# modbusbox.net
KiCad netlist of a schematic drawn in EAGLE
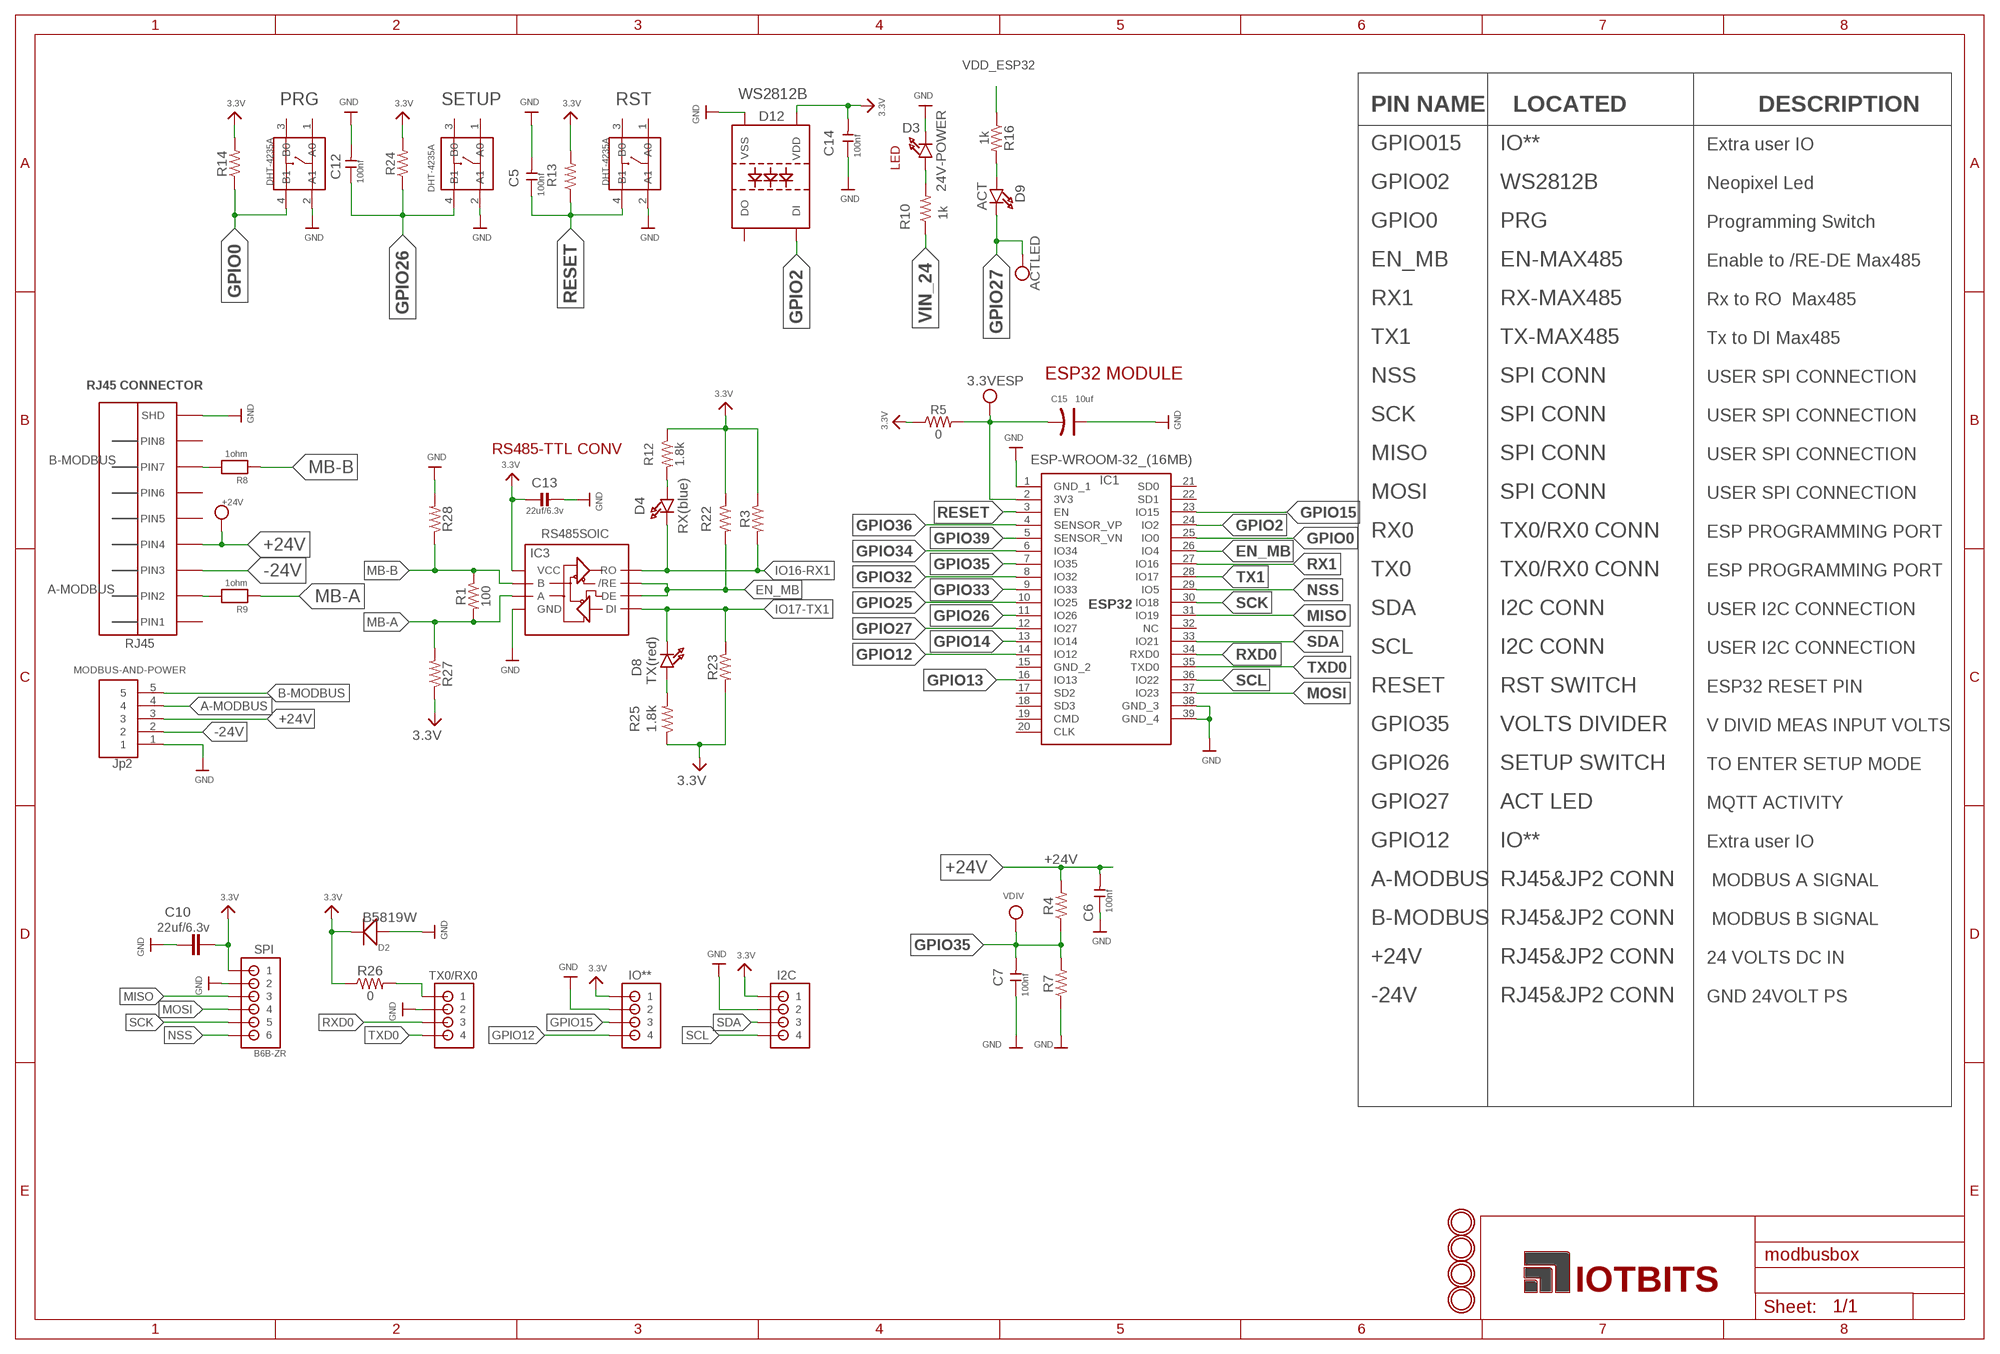
[diagram p0: schematic, sheet 1]

(export (version "E")
  (design (tool "Eeschema 10.0.6"))
  (components
    (comp (ref "+24V")
      (value "TESTPOINTROUND2MM")
      (footprint "eagle-import:TESTPOINT_ROUND_2MM")
      (libsource (lib "eagle-import") (part "TESTPOINTROUND2MM"))
    )
    (comp (ref "3.3VESP")
      (value "TESTPOINTROUND2MM")
      (footprint "eagle-import:TESTPOINT_ROUND_2MM")
      (libsource (lib "eagle-import") (part "TESTPOINTROUND2MM"))
    )
    (comp (ref "ACTLED")
      (value "TESTPOINTROUND2MM")
      (footprint "eagle-import:TESTPOINT_ROUND_2MM")
      (libsource (lib "eagle-import") (part "TESTPOINTROUND2MM"))
    )
    (comp (ref "C5")
      (value "100nf")
      (footprint "eagle-import:C0603")
      (fields (field (name "MPN") "CC0603KRX7R9BB104") (field (name "SPICEPREFIX") "C"))
      (libsource (lib "eagle-import") (part "CERAMIC-100NF-50V-10%-X7R(0603)"))
    )
    (comp (ref "C6")
      (value "100nf")
      (footprint "eagle-import:C0603")
      (fields (field (name "MPN") "CC0603KRX7R9BB104"))
      (libsource (lib "eagle-import") (part "CERAMIC-100NF-50V-10%-X7R(0603)"))
    )
    (comp (ref "C7")
      (value "100nf")
      (footprint "eagle-import:C0603")
      (fields (field (name "MPN") "CC0603KRX7R9BB104"))
      (libsource (lib "eagle-import") (part "CERAMIC-100NF-50V-10%-X7R(0603)"))
    )
    (comp (ref "C10")
      (value "22uf/6.3v")
      (footprint "eagle-import:0805-CAP-LARGEPADS")
      (libsource (lib "eagle-import") (part "CAP0805-CAP-LARGEPADS"))
    )
    (comp (ref "C12")
      (value "100nf")
      (footprint "eagle-import:C0603")
      (fields (field (name "MPN") "CC0603KRX7R9BB104") (field (name "SPICEPREFIX") "C"))
      (libsource (lib "eagle-import") (part "CERAMIC-100NF-50V-10%-X7R(0603)"))
    )
    (comp (ref "C13")
      (value "22uf/6.3v")
      (footprint "eagle-import:_0805")
      (libsource (lib "eagle-import") (part "CAP_CERAMIC_0805"))
    )
    (comp (ref "C14")
      (value "100nf")
      (footprint "eagle-import:C0603")
      (fields (field (name "MPN") "CC0603KRX7R9BB104"))
      (libsource (lib "eagle-import") (part "CERAMIC-100NF-50V-10%-X7R(0603)"))
    )
    (comp (ref "C15")
      (value "10uf")
      (footprint "eagle-import:AVX-A")
      (fields (field (name "MPN") "TAJA106K010RNJ"))
      (libsource (lib "eagle-import") (part "TANTALUM-SMD-10UF-10V-10%(AVX-A)"))
    )
    (comp (ref "D2")
      (value "B5819W")
      (footprint "eagle-import:SOD-123")
      (libsource (lib "eagle-import") (part "SMD-DIODE-SCHOTTKY-20V-1A(SOD-123)"))
    )
    (comp (ref "D3")
      (value "24V-POWER")
      (footprint "eagle-import:CHIPLED_0603")
      (libsource (lib "eagle-import") (part "LED0603"))
    )
    (comp (ref "D4")
      (value "RX(blue)")
      (footprint "eagle-import:CHIPLED_0603")
      (libsource (lib "eagle-import") (part "LED0603"))
    )
    (comp (ref "D8")
      (value "TX(red)")
      (footprint "eagle-import:CHIPLED_0603")
      (libsource (lib "eagle-import") (part "LED0603"))
    )
    (comp (ref "D9")
      (value "ACT")
      (footprint "eagle-import:CHIPLED_0603")
      (libsource (lib "eagle-import") (part "LED0603"))
    )
    (comp (ref "D12")
      (value "WS2812B")
      (footprint "eagle-import:WS2812B")
      (libsource (lib "eagle-import") (part "WS2812B"))
    )
    (comp (ref "I2C")
      (value "B4B-ZR")
      (footprint "eagle-import:B4B-ZR")
      (libsource (lib "eagle-import") (part "B4B-ZR"))
    )
    (comp (ref "IC1")
      (value "ESP-WROOM-32_(16MB)")
      (footprint "eagle-import:ESP32WROOM32D")
      (fields
        (field (name "MANUFACTURER_PART_NUMBER") "ESP-WROOM-32 (16MB)")
        (field (name "MOUSER_PART_NUMBER") "356-ESPWROOM3216MB")
      )
      (libsource (lib "eagle-import") (part "ESP-WROOM-32_(16MB)"))
    )
    (comp (ref "IC3")
      (value "RS485SOIC")
      (footprint "eagle-import:SO08")
      (libsource (lib "eagle-import") (part "RS485SOIC"))
    )
    (comp (ref "IO**")
      (value "B4B-ZR")
      (footprint "eagle-import:B4B-ZR")
      (libsource (lib "eagle-import") (part "B4B-ZR"))
    )
    (comp (ref "MODBUS-AND-POWER")
      (value "5PIN")
      (footprint "eagle-import:B5B-PH-K-S")
      (libsource (lib "eagle-import") (part "5PIN"))
    )
    (comp (ref "PRG")
      (value "DHT-4235A")
      (footprint "eagle-import:SW4-SMD-4.2X3.2X2.5MM")
      (fields (field (name "SPICEPREFIX") "E"))
      (libsource (lib "eagle-import") (part "SMD-BUTTON-TOP-DHT-4235A(4P-4.2X3.2MM)"))
    )
    (comp (ref "R1")
      (value "100")
      (footprint "eagle-import:0603")
      (libsource (lib "eagle-import") (part "100OHM-0603-1/4W-5%"))
    )
    (comp (ref "R3")
      (value "10KOHM-0603-1/10W-1%")
      (footprint "eagle-import:0603")
      (libsource (lib "eagle-import") (part "10KOHM-0603-1/10W-1%"))
    )
    (comp (ref "R4")
      (value "100k")
      (footprint "eagle-import:0603")
      (libsource (lib "eagle-import") (part "10KOHM-0603-1/10W-1%"))
    )
    (comp (ref "R5")
      (value "0")
      (footprint "eagle-import:0603")
      (libsource (lib "eagle-import") (part "0OHM-0603-1/10W-5%"))
    )
    (comp (ref "R7")
      (value "15k")
      (footprint "eagle-import:0603")
      (libsource (lib "eagle-import") (part "10KOHM-0603-1/10W-1%"))
    )
    (comp (ref "R8")
      (value "1ohm")
      (footprint "eagle-import:0603")
      (libsource (lib "eagle-import") (part "RESISTOR0603"))
    )
    (comp (ref "R9")
      (value "1ohm")
      (footprint "eagle-import:0603")
      (libsource (lib "eagle-import") (part "RESISTOR0603"))
    )
    (comp (ref "R10")
      (value "1k")
      (footprint "eagle-import:0603")
      (libsource (lib "eagle-import") (part "1KOHM-0603-1/10W-1%"))
    )
    (comp (ref "R12")
      (value "1.8k")
      (footprint "eagle-import:0603")
      (libsource (lib "eagle-import") (part "1.8KOHM-0603-1/10W-1%"))
    )
    (comp (ref "R13")
      (value "10KOHM-0603-1/10W-1%")
      (footprint "eagle-import:0603")
      (fields (field (name "SPICEPREFIX") "R"))
      (libsource (lib "eagle-import") (part "10KOHM-0603-1/10W-1%"))
    )
    (comp (ref "R14")
      (value "10KOHM-0603-1/10W-1%")
      (footprint "eagle-import:0603")
      (fields (field (name "SPICEPREFIX") "R"))
      (libsource (lib "eagle-import") (part "10KOHM-0603-1/10W-1%"))
    )
    (comp (ref "R16")
      (value "1k")
      (footprint "eagle-import:0603")
      (libsource (lib "eagle-import") (part "1KOHM-0603-1/10W-1%"))
    )
    (comp (ref "R22")
      (value "10KOHM-0603-1/10W-1%")
      (footprint "eagle-import:0603")
      (libsource (lib "eagle-import") (part "10KOHM-0603-1/10W-1%"))
    )
    (comp (ref "R23")
      (value "10KOHM-0603-1/10W-1%")
      (footprint "eagle-import:0603")
      (libsource (lib "eagle-import") (part "10KOHM-0603-1/10W-1%"))
    )
    (comp (ref "R24")
      (value "10KOHM-0603-1/10W-1%")
      (footprint "eagle-import:0603")
      (fields (field (name "SPICEPREFIX") "R"))
      (libsource (lib "eagle-import") (part "10KOHM-0603-1/10W-1%"))
    )
    (comp (ref "R25")
      (value "1.8k")
      (footprint "eagle-import:0603")
      (libsource (lib "eagle-import") (part "1.8KOHM-0603-1/10W-1%"))
    )
    (comp (ref "R26")
      (value "0")
      (footprint "eagle-import:0603")
      (libsource (lib "eagle-import") (part "0OHM-0603-1/10W-5%"))
    )
    (comp (ref "R27")
      (value "2.2k")
      (footprint "eagle-import:0603")
      (libsource (lib "eagle-import") (part "10KOHM-0603-1/10W-1%"))
    )
    (comp (ref "R28")
      (value "2.2k")
      (footprint "eagle-import:0603")
      (libsource (lib "eagle-import") (part "10KOHM-0603-1/10W-1%"))
    )
    (comp (ref "RJ45")
      (value "RJ45 CONNECTOR")
      (footprint "eagle-import:RJ45")
      (libsource (lib "eagle-import") (part "RJ45"))
    )
    (comp (ref "RST")
      (value "DHT-4235A")
      (footprint "eagle-import:SW4-SMD-4.2X3.2X2.5MM")
      (fields (field (name "SPICEPREFIX") "E"))
      (libsource (lib "eagle-import") (part "SMD-BUTTON-TOP-DHT-4235A(4P-4.2X3.2MM)"))
    )
    (comp (ref "SETUP")
      (value "DHT-4235A")
      (footprint "eagle-import:SW4-SMD-4.2X3.2X2.5MM")
      (fields (field (name "SPICEPREFIX") "S"))
      (libsource (lib "eagle-import") (part "SMD-BUTTON-TOP-DHT-4235A(4P-4.2X3.2MM)"))
    )
    (comp (ref "SPI")
      (value "B6B-ZR")
      (footprint "eagle-import:B6B-ZR")
      (libsource (lib "eagle-import") (part "B6B-ZR"))
    )
    (comp (ref "TX0/RX0")
      (value "B4B-ZR")
      (footprint "eagle-import:B4B-ZR")
      (libsource (lib "eagle-import") (part "B4B-ZR"))
    )
    (comp (ref "U$30")
      (value "MOUNTINGHOLE3.0THIN")
      (footprint "eagle-import:MOUNTINGHOLE_3.0_PLATEDTHIN")
      (libsource (lib "eagle-import") (part "MOUNTINGHOLE3.0THIN"))
    )
    (comp (ref "U$31")
      (value "MOUNTINGHOLE3.0THIN")
      (footprint "eagle-import:MOUNTINGHOLE_3.0_PLATEDTHIN")
      (libsource (lib "eagle-import") (part "MOUNTINGHOLE3.0THIN"))
    )
    (comp (ref "U$33")
      (value "MOUNTINGHOLE3.0THIN")
      (footprint "eagle-import:MOUNTINGHOLE_3.0_PLATEDTHIN")
      (libsource (lib "eagle-import") (part "MOUNTINGHOLE3.0THIN"))
    )
    (comp (ref "U$35")
      (value "MOUNTINGHOLE3.0THIN")
      (footprint "eagle-import:MOUNTINGHOLE_3.0_PLATEDTHIN")
      (libsource (lib "eagle-import") (part "MOUNTINGHOLE3.0THIN"))
    )
    (comp (ref "VDIV")
      (value "TESTPOINTROUND2MM")
      (footprint "eagle-import:TESTPOINT_ROUND_2MM")
      (libsource (lib "eagle-import") (part "TESTPOINTROUND2MM"))
    )
  )
  (nets
    (net (code "1") (name "+24V") (class "Default")
      (node (ref "+24V") (pin "P$1") (pinfunction "P$1_P$1") (pintype "bidirectional"))
      (node (ref "C6") (pin "2") (pinfunction "2_2") (pintype "passive"))
      (node (ref "MODBUS-AND-POWER") (pin "3") (pinfunction "3_3") (pintype "bidirectional"))
      (node (ref "R4") (pin "2") (pinfunction "2_2") (pintype "passive"))
      (node (ref "RJ45") (pin "P$10") (pinfunction "PIN4_P$10") (pintype "bidirectional"))
    )
    (net (code "2") (name "-24V") (class "Default")
      (node (ref "MODBUS-AND-POWER") (pin "2") (pinfunction "2_2") (pintype "bidirectional"))
      (node (ref "RJ45") (pin "P$9") (pinfunction "PIN3_P$9") (pintype "bidirectional"))
    )
    (net (code "3") (name "/VDD_ESP32") (class "Default")
      (node (ref "3.3VESP") (pin "P$1") (pinfunction "P$1_P$1") (pintype "bidirectional"))
      (node (ref "C15") (pin "-") (pinfunction "-_-") (pintype "passive"))
      (node (ref "IC1") (pin "2") (pinfunction "3V3_2") (pintype "bidirectional"))
      (node (ref "R16") (pin "1") (pinfunction "1_1") (pintype "passive"))
      (node (ref "R5") (pin "2") (pinfunction "2_2") (pintype "passive"))
    )
    (net (code "4") (name "3.3V") (class "Default")
      (node (ref "C10") (pin "1") (pinfunction "1_1") (pintype "passive"))
      (node (ref "C13") (pin "1") (pinfunction "1_1") (pintype "passive"))
      (node (ref "C14") (pin "2") (pinfunction "2_2") (pintype "passive"))
      (node (ref "D12") (pin "1") (pinfunction "VDD_1") (pintype "bidirectional"))
      (node (ref "D2") (pin "-") (pinfunction "-_-") (pintype "passive"))
      (node (ref "I2C") (pin "1") (pinfunction "1_1") (pintype "bidirectional"))
      (node (ref "IC3") (pin "8") (pinfunction "VCC_8") (pintype "bidirectional"))
      (node (ref "IO**") (pin "1") (pinfunction "1_1") (pintype "bidirectional"))
      (node (ref "R12") (pin "1") (pinfunction "1_1") (pintype "passive"))
      (node (ref "R13") (pin "2") (pinfunction "2_2") (pintype "passive"))
      (node (ref "R14") (pin "2") (pinfunction "2_2") (pintype "passive"))
      (node (ref "R22") (pin "1") (pinfunction "1_1") (pintype "passive"))
      (node (ref "R23") (pin "2") (pinfunction "2_2") (pintype "passive"))
      (node (ref "R24") (pin "2") (pinfunction "2_2") (pintype "passive"))
      (node (ref "R25") (pin "1") (pinfunction "1_1") (pintype "passive"))
      (node (ref "R26") (pin "1") (pinfunction "1_1") (pintype "passive"))
      (node (ref "R27") (pin "1") (pinfunction "1_1") (pintype "passive"))
      (node (ref "R3") (pin "1") (pinfunction "1_1") (pintype "passive"))
      (node (ref "R5") (pin "1") (pinfunction "1_1") (pintype "passive"))
      (node (ref "SPI") (pin "1") (pinfunction "1_1") (pintype "bidirectional"))
    )
    (net (code "5") (name "A-MODBUS") (class "Default")
      (node (ref "MODBUS-AND-POWER") (pin "4") (pinfunction "4_4") (pintype "bidirectional"))
      (node (ref "R9") (pin "2") (pinfunction "2_2") (pintype "passive"))
      (node (ref "RJ45") (pin "P$3") (pinfunction "PIN2_P$3") (pintype "bidirectional"))
    )
    (net (code "6") (name "B-MODBUS") (class "Default")
      (node (ref "MODBUS-AND-POWER") (pin "5") (pinfunction "5_5") (pintype "bidirectional"))
      (node (ref "R8") (pin "2") (pinfunction "2_2") (pintype "passive"))
      (node (ref "RJ45") (pin "P$6") (pinfunction "PIN7_P$6") (pintype "bidirectional"))
    )
    (net (code "7") (name "EN_MB") (class "Default")
      (node (ref "IC1") (pin "26") (pinfunction "IO4_26") (pintype "bidirectional"))
      (node (ref "IC3") (pin "2") (pinfunction "/RE_2") (pintype "bidirectional"))
      (node (ref "IC3") (pin "3") (pinfunction "DE_3") (pintype "bidirectional"))
      (node (ref "R22") (pin "2") (pinfunction "2_2") (pintype "passive"))
    )
    (net (code "8") (name "GND") (class "Default")
      (node (ref "C10") (pin "2") (pinfunction "2_2") (pintype "passive"))
      (node (ref "C12") (pin "2") (pinfunction "2_2") (pintype "passive"))
      (node (ref "C13") (pin "2") (pinfunction "2_2") (pintype "passive"))
      (node (ref "C14") (pin "1") (pinfunction "1_1") (pintype "passive"))
      (node (ref "C15") (pin "+") (pinfunction "+_+") (pintype "passive"))
      (node (ref "C5") (pin "2") (pinfunction "2_2") (pintype "passive"))
      (node (ref "C6") (pin "1") (pinfunction "1_1") (pintype "passive"))
      (node (ref "C7") (pin "1") (pinfunction "1_1") (pintype "passive"))
      (node (ref "D12") (pin "3") (pinfunction "VSS_3") (pintype "bidirectional"))
      (node (ref "D2") (pin "+") (pinfunction "+_+") (pintype "passive"))
      (node (ref "D3") (pin "C") (pinfunction "C_C") (pintype "passive"))
      (node (ref "I2C") (pin "2") (pinfunction "2_2") (pintype "bidirectional"))
      (node (ref "IC1") (pin "1") (pinfunction "GND_1_1") (pintype "bidirectional"))
      (node (ref "IC1") (pin "38") (pinfunction "GND_3_38") (pintype "bidirectional"))
      (node (ref "IC1") (pin "39") (pinfunction "GND_4_39") (pintype "bidirectional"))
      (node (ref "IC3") (pin "5") (pinfunction "GND_5") (pintype "bidirectional"))
      (node (ref "IO**") (pin "2") (pinfunction "2_2") (pintype "bidirectional"))
      (node (ref "MODBUS-AND-POWER") (pin "1") (pinfunction "1_1") (pintype "bidirectional"))
      (node (ref "PRG") (pin "2") (pinfunction "A1_2") (pintype "bidirectional"))
      (node (ref "R28") (pin "2") (pinfunction "2_2") (pintype "passive"))
      (node (ref "R7") (pin "1") (pinfunction "1_1") (pintype "passive"))
      (node (ref "RJ45") (pin "P$1") (pinfunction "SHD_P$1") (pintype "bidirectional"))
      (node (ref "RJ45") (pin "P$2") (pinfunction "SHD_P$2") (pintype "bidirectional"))
      (node (ref "RST") (pin "2") (pinfunction "A1_2") (pintype "bidirectional"))
      (node (ref "SETUP") (pin "2") (pinfunction "A1_2") (pintype "bidirectional"))
      (node (ref "SPI") (pin "2") (pinfunction "2_2") (pintype "bidirectional"))
      (node (ref "TX0/RX0") (pin "2") (pinfunction "2_2") (pintype "bidirectional"))
    )
    (net (code "9") (name "GPIO0") (class "Default")
      (node (ref "IC1") (pin "25") (pinfunction "IO0_25") (pintype "bidirectional"))
      (node (ref "PRG") (pin "4") (pinfunction "B1_4") (pintype "bidirectional"))
      (node (ref "R14") (pin "1") (pinfunction "1_1") (pintype "passive"))
    )
    (net (code "10") (name "GPIO2") (class "Default")
      (node (ref "D12") (pin "4") (pinfunction "DI_4") (pintype "bidirectional"))
      (node (ref "IC1") (pin "24") (pinfunction "IO2_24") (pintype "bidirectional"))
    )
    (net (code "11") (name "GPIO12") (class "Default")
      (node (ref "IC1") (pin "14") (pinfunction "IO12_14") (pintype "bidirectional"))
      (node (ref "IO**") (pin "4") (pinfunction "4_4") (pintype "bidirectional"))
    )
    (net (code "12") (name "GPIO13") (class "Default")
      (node (ref "IC1") (pin "16") (pinfunction "IO13_16") (pintype "bidirectional"))
    )
    (net (code "13") (name "GPIO14") (class "Default")
      (node (ref "IC1") (pin "13") (pinfunction "IO14_13") (pintype "bidirectional"))
    )
    (net (code "14") (name "GPIO15") (class "Default")
      (node (ref "IC1") (pin "23") (pinfunction "IO15_23") (pintype "bidirectional"))
      (node (ref "IO**") (pin "3") (pinfunction "3_3") (pintype "bidirectional"))
    )
    (net (code "15") (name "GPIO25") (class "Default")
      (node (ref "IC1") (pin "10") (pinfunction "IO25_10") (pintype "bidirectional"))
    )
    (net (code "16") (name "GPIO26") (class "Default")
      (node (ref "C12") (pin "1") (pinfunction "1_1") (pintype "passive"))
      (node (ref "IC1") (pin "11") (pinfunction "IO26_11") (pintype "bidirectional"))
      (node (ref "R24") (pin "1") (pinfunction "1_1") (pintype "passive"))
      (node (ref "SETUP") (pin "4") (pinfunction "B1_4") (pintype "bidirectional"))
    )
    (net (code "17") (name "GPIO27") (class "Default")
      (node (ref "ACTLED") (pin "P$1") (pinfunction "P$1_P$1") (pintype "bidirectional"))
      (node (ref "D9") (pin "C") (pinfunction "C_C") (pintype "passive"))
      (node (ref "IC1") (pin "12") (pinfunction "IO27_12") (pintype "bidirectional"))
    )
    (net (code "18") (name "GPIO32") (class "Default")
      (node (ref "IC1") (pin "8") (pinfunction "IO32_8") (pintype "bidirectional"))
    )
    (net (code "19") (name "GPIO33") (class "Default")
      (node (ref "IC1") (pin "9") (pinfunction "IO33_9") (pintype "bidirectional"))
    )
    (net (code "20") (name "GPIO34") (class "Default")
      (node (ref "IC1") (pin "6") (pinfunction "IO34_6") (pintype "bidirectional"))
    )
    (net (code "21") (name "GPIO35") (class "Default")
      (node (ref "C7") (pin "2") (pinfunction "2_2") (pintype "passive"))
      (node (ref "IC1") (pin "7") (pinfunction "IO35_7") (pintype "bidirectional"))
      (node (ref "R4") (pin "1") (pinfunction "1_1") (pintype "passive"))
      (node (ref "R7") (pin "2") (pinfunction "2_2") (pintype "passive"))
      (node (ref "VDIV") (pin "P$1") (pinfunction "P$1_P$1") (pintype "bidirectional"))
    )
    (net (code "22") (name "GPIO36") (class "Default")
      (node (ref "IC1") (pin "4") (pinfunction "SENSOR_VP_4") (pintype "bidirectional"))
    )
    (net (code "23") (name "GPIO39") (class "Default")
      (node (ref "IC1") (pin "5") (pinfunction "SENSOR_VN_5") (pintype "bidirectional"))
    )
    (net (code "24") (name "IO16-RX1") (class "Default")
      (node (ref "D4") (pin "C") (pinfunction "C_C") (pintype "passive"))
      (node (ref "IC3") (pin "1") (pinfunction "RO_1") (pintype "bidirectional"))
      (node (ref "R3") (pin "2") (pinfunction "2_2") (pintype "passive"))
    )
    (net (code "25") (name "IO17-TX1") (class "Default")
      (node (ref "D8") (pin "C") (pinfunction "C_C") (pintype "passive"))
      (node (ref "IC3") (pin "4") (pinfunction "DI_4") (pintype "bidirectional"))
      (node (ref "R23") (pin "1") (pinfunction "1_1") (pintype "passive"))
    )
    (net (code "26") (name "MB-A") (class "Default")
      (node (ref "IC3") (pin "6") (pinfunction "A_6") (pintype "bidirectional"))
      (node (ref "R1") (pin "2") (pinfunction "2_2") (pintype "passive"))
      (node (ref "R27") (pin "2") (pinfunction "2_2") (pintype "passive"))
      (node (ref "R9") (pin "1") (pinfunction "1_1") (pintype "passive"))
    )
    (net (code "27") (name "MB-B") (class "Default")
      (node (ref "IC3") (pin "7") (pinfunction "B_7") (pintype "bidirectional"))
      (node (ref "R1") (pin "1") (pinfunction "1_1") (pintype "passive"))
      (node (ref "R28") (pin "1") (pinfunction "1_1") (pintype "passive"))
      (node (ref "R8") (pin "1") (pinfunction "1_1") (pintype "passive"))
    )
    (net (code "28") (name "MISO") (class "Default")
      (node (ref "IC1") (pin "31") (pinfunction "IO19_31") (pintype "bidirectional"))
      (node (ref "SPI") (pin "3") (pinfunction "3_3") (pintype "bidirectional"))
    )
    (net (code "29") (name "MOSI") (class "Default")
      (node (ref "IC1") (pin "37") (pinfunction "IO23_37") (pintype "bidirectional"))
      (node (ref "SPI") (pin "4") (pinfunction "4_4") (pintype "bidirectional"))
    )
    (net (code "30") (name "NSS") (class "Default")
      (node (ref "IC1") (pin "29") (pinfunction "IO5_29") (pintype "bidirectional"))
      (node (ref "SPI") (pin "6") (pinfunction "6_6") (pintype "bidirectional"))
    )
    (net (code "31") (name "Net-(D3-PadA)") (class "Default")
      (node (ref "D3") (pin "A") (pinfunction "A_A") (pintype "passive"))
      (node (ref "R10") (pin "2") (pinfunction "2_2") (pintype "passive"))
    )
    (net (code "32") (name "Net-(D4-PadA)") (class "Default")
      (node (ref "D4") (pin "A") (pinfunction "A_A") (pintype "passive"))
      (node (ref "R12") (pin "2") (pinfunction "2_2") (pintype "passive"))
    )
    (net (code "33") (name "Net-(D8-PadA)") (class "Default")
      (node (ref "D8") (pin "A") (pinfunction "A_A") (pintype "passive"))
      (node (ref "R25") (pin "2") (pinfunction "2_2") (pintype "passive"))
    )
    (net (code "34") (name "Net-(D9-PadA)") (class "Default")
      (node (ref "D9") (pin "A") (pinfunction "A_A") (pintype "passive"))
      (node (ref "R16") (pin "2") (pinfunction "2_2") (pintype "passive"))
    )
    (net (code "35") (name "Net-(R26-Pad2)") (class "Default")
      (node (ref "R26") (pin "2") (pinfunction "2_2") (pintype "passive"))
      (node (ref "TX0/RX0") (pin "1") (pinfunction "1_1") (pintype "bidirectional"))
    )
    (net (code "36") (name "RESET") (class "Default")
      (node (ref "C5") (pin "1") (pinfunction "1_1") (pintype "passive"))
      (node (ref "IC1") (pin "3") (pinfunction "EN_3") (pintype "bidirectional"))
      (node (ref "R13") (pin "1") (pinfunction "1_1") (pintype "passive"))
      (node (ref "RST") (pin "4") (pinfunction "B1_4") (pintype "bidirectional"))
    )
    (net (code "37") (name "RX1") (class "Default")
      (node (ref "IC1") (pin "27") (pinfunction "IO16_27") (pintype "bidirectional"))
    )
    (net (code "38") (name "RXD0") (class "Default")
      (node (ref "IC1") (pin "34") (pinfunction "RXD0_34") (pintype "bidirectional"))
      (node (ref "TX0/RX0") (pin "3") (pinfunction "3_3") (pintype "bidirectional"))
    )
    (net (code "39") (name "SCK") (class "Default")
      (node (ref "IC1") (pin "30") (pinfunction "IO18_30") (pintype "bidirectional"))
      (node (ref "SPI") (pin "5") (pinfunction "5_5") (pintype "bidirectional"))
    )
    (net (code "40") (name "SCL") (class "Default")
      (node (ref "I2C") (pin "4") (pinfunction "4_4") (pintype "bidirectional"))
      (node (ref "IC1") (pin "36") (pinfunction "IO22_36") (pintype "bidirectional"))
    )
    (net (code "41") (name "SDA") (class "Default")
      (node (ref "I2C") (pin "3") (pinfunction "3_3") (pintype "bidirectional"))
      (node (ref "IC1") (pin "33") (pinfunction "IO21_33") (pintype "bidirectional"))
    )
    (net (code "42") (name "TX1") (class "Default")
      (node (ref "IC1") (pin "28") (pinfunction "IO17_28") (pintype "bidirectional"))
    )
    (net (code "43") (name "TXD0") (class "Default")
      (node (ref "IC1") (pin "35") (pinfunction "TXD0_35") (pintype "bidirectional"))
      (node (ref "TX0/RX0") (pin "4") (pinfunction "4_4") (pintype "bidirectional"))
    )
    (net (code "44") (name "VIN_24") (class "Default")
      (node (ref "R10") (pin "1") (pinfunction "1_1") (pintype "passive"))
    )
    (net (code "45") (name "unconnected-(D12-DO-Pad2)") (class "Default")
      (node (ref "D12") (pin "2") (pinfunction "DO_2") (pintype "bidirectional"))
    )
    (net (code "46") (name "unconnected-(IC1-CLK-Pad20)") (class "Default")
      (node (ref "IC1") (pin "20") (pinfunction "CLK_20") (pintype "bidirectional"))
    )
    (net (code "47") (name "unconnected-(IC1-CMD-Pad19)") (class "Default")
      (node (ref "IC1") (pin "19") (pinfunction "CMD_19") (pintype "bidirectional"))
    )
    (net (code "48") (name "unconnected-(IC1-GND_2-Pad15)") (class "Default")
      (node (ref "IC1") (pin "15") (pinfunction "GND_2_15") (pintype "bidirectional"))
    )
    (net (code "49") (name "unconnected-(IC1-NC-Pad32)") (class "Default")
      (node (ref "IC1") (pin "32") (pinfunction "NC_32") (pintype "no_connect"))
    )
    (net (code "50") (name "unconnected-(IC1-SD0-Pad21)") (class "Default")
      (node (ref "IC1") (pin "21") (pinfunction "SD0_21") (pintype "bidirectional"))
    )
    (net (code "51") (name "unconnected-(IC1-SD1-Pad22)") (class "Default")
      (node (ref "IC1") (pin "22") (pinfunction "SD1_22") (pintype "bidirectional"))
    )
    (net (code "52") (name "unconnected-(IC1-SD2-Pad17)") (class "Default")
      (node (ref "IC1") (pin "17") (pinfunction "SD2_17") (pintype "bidirectional"))
    )
    (net (code "53") (name "unconnected-(IC1-SD3-Pad18)") (class "Default")
      (node (ref "IC1") (pin "18") (pinfunction "SD3_18") (pintype "bidirectional"))
    )
    (net (code "54") (name "unconnected-(PRG-A0-Pad1)") (class "Default")
      (node (ref "PRG") (pin "1") (pinfunction "A0_1") (pintype "bidirectional"))
    )
    (net (code "55") (name "unconnected-(PRG-B0-Pad3)") (class "Default")
      (node (ref "PRG") (pin "3") (pinfunction "B0_3") (pintype "bidirectional"))
    )
    (net (code "56") (name "unconnected-(RJ45-PIN1-PadP$8)") (class "Default")
      (node (ref "RJ45") (pin "P$8") (pinfunction "PIN1_P$8") (pintype "bidirectional"))
    )
    (net (code "57") (name "unconnected-(RJ45-PIN5-PadP$7)") (class "Default")
      (node (ref "RJ45") (pin "P$7") (pinfunction "PIN5_P$7") (pintype "bidirectional"))
    )
    (net (code "58") (name "unconnected-(RJ45-PIN6-PadP$5)") (class "Default")
      (node (ref "RJ45") (pin "P$5") (pinfunction "PIN6_P$5") (pintype "bidirectional"))
    )
    (net (code "59") (name "unconnected-(RJ45-PIN8-PadP$4)") (class "Default")
      (node (ref "RJ45") (pin "P$4") (pinfunction "PIN8_P$4") (pintype "bidirectional"))
    )
    (net (code "60") (name "unconnected-(RST-A0-Pad1)") (class "Default")
      (node (ref "RST") (pin "1") (pinfunction "A0_1") (pintype "bidirectional"))
    )
    (net (code "61") (name "unconnected-(RST-B0-Pad3)") (class "Default")
      (node (ref "RST") (pin "3") (pinfunction "B0_3") (pintype "bidirectional"))
    )
    (net (code "62") (name "unconnected-(SETUP-A0-Pad1)") (class "Default")
      (node (ref "SETUP") (pin "1") (pinfunction "A0_1") (pintype "bidirectional"))
    )
    (net (code "63") (name "unconnected-(SETUP-B0-Pad3)") (class "Default")
      (node (ref "SETUP") (pin "3") (pinfunction "B0_3") (pintype "bidirectional"))
    )
  )
)
